# Wings_pwm.net
KiCad netlist of a schematic drawn in Altium Designer
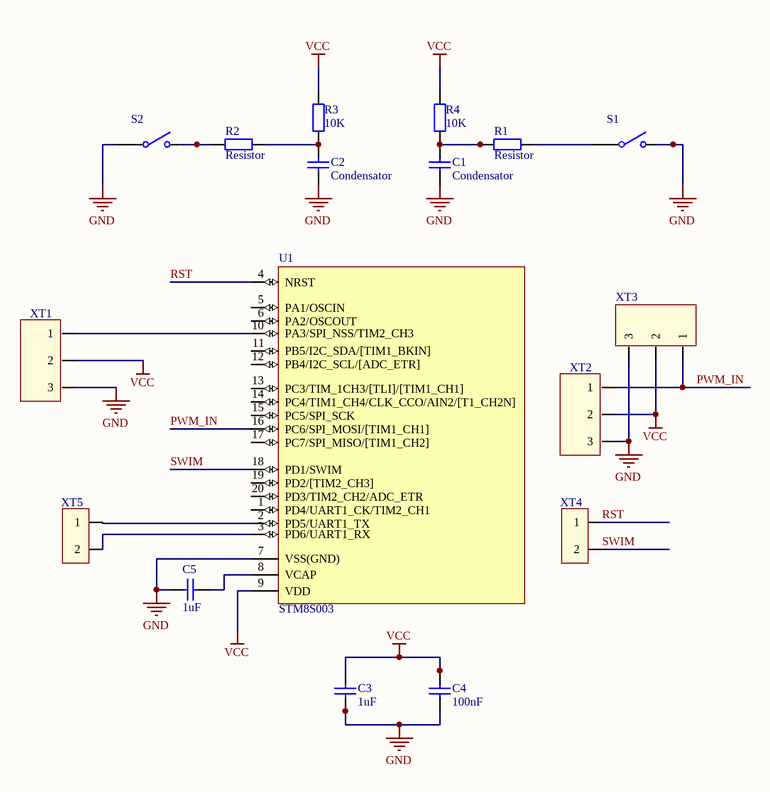
[diagram p0: Wings_pwm.SchDoc]

(export (version "E")
  (design (tool "Eeschema 10.0.6"))
  (components
    (comp (ref "C1")
      (value "Condensator")
      (footprint "A_H_pcb_lib:C0603")
      (libsource (lib "A_H_sch_lib") (part "Condensator"))
    )
    (comp (ref "C2")
      (value "Condensator")
      (footprint "A_H_pcb_lib:C0603")
      (libsource (lib "A_H_sch_lib") (part "Condensator"))
    )
    (comp (ref "C3")
      (value "1uF")
      (footprint "A_H_pcb_lib:C0603")
      (libsource (lib "A_H_sch_lib") (part "Condensator"))
    )
    (comp (ref "C4")
      (value "100nF")
      (footprint "A_H_pcb_lib:C0603")
      (libsource (lib "A_H_sch_lib") (part "Condensator"))
    )
    (comp (ref "C5")
      (value "1uF")
      (footprint "A_H_pcb_lib:C0603")
      (libsource (lib "A_H_sch_lib") (part "Condensator"))
    )
    (comp (ref "R1")
      (value "Resistor")
      (footprint "A_H_pcb_lib:R0603")
      (libsource (lib "A_H_sch_lib") (part "Resistor"))
    )
    (comp (ref "R2")
      (value "Resistor")
      (footprint "A_H_pcb_lib:R0603")
      (libsource (lib "A_H_sch_lib") (part "Resistor"))
    )
    (comp (ref "R3") (value "10K") (footprint "A_H_pcb_lib:R0603") (libsource (lib "") (part "Resistor_1")))
    (comp (ref "R4") (value "10K") (footprint "A_H_pcb_lib:R0603") (libsource (lib "") (part "Resistor_1")))
    (comp (ref "S1")
      (value "*")
      (footprint "A_H_pcb_lib:Tact_switch_smd")
      (libsource (lib "A_H_sch_lib") (part "Tact_switch"))
    )
    (comp (ref "S2")
      (value "*")
      (footprint "A_H_pcb_lib:Tact_switch_smd")
      (libsource (lib "A_H_sch_lib") (part "Tact_switch"))
    )
    (comp (ref "U1")
      (value "STM8S003")
      (footprint "A_H_pcb_lib:STM8S003_TSOP20")
      (libsource (lib "A_H_sch_lib") (part "STM8S003"))
    )
    (comp (ref "XT1")
      (value "*")
      (footprint "A_H_pcb_lib:flat_3pad")
      (libsource (lib "") (part "Pins 3x2.54_1"))
    )
    (comp (ref "XT2")
      (value "*")
      (footprint "A_H_pcb_lib:flat_3pad")
      (libsource (lib "") (part "Pins 3x2.54_1"))
    )
    (comp (ref "XT3")
      (value "*")
      (footprint "A_H_pcb_lib:flat_3pad")
      (libsource (lib "A_H_sch_lib") (part "Pins 3x2.54"))
    )
    (comp (ref "XT4")
      (value "*")
      (footprint "A_H_pcb_lib:Pins 2x2.54")
      (libsource (lib "A_H_sch_lib") (part "Pins 2x2.54"))
    )
    (comp (ref "XT5")
      (value "*")
      (footprint "A_H_pcb_lib:Pins 2x2.54")
      (libsource (lib "A_H_sch_lib") (part "Pins 2x2.54"))
    )
  )
  (nets
    (net (code "1") (name "/PWM_IN") (class "Default")
      (node (ref "U1") (pin "16") (pinfunction "PC6/SPI_MOSI/[TIM1_CH1]_16") (pintype "bidirectional"))
      (node (ref "XT2") (pin "1") (pinfunction "1_1") (pintype "passive"))
      (node (ref "XT3") (pin "1") (pinfunction "1_1") (pintype "passive"))
    )
    (net (code "2") (name "/RST") (class "Default")
      (node (ref "U1") (pin "4") (pinfunction "NRST_4") (pintype "bidirectional"))
      (node (ref "XT4") (pin "1") (pinfunction "1_1") (pintype "passive"))
    )
    (net (code "3") (name "/SWIM") (class "Default")
      (node (ref "U1") (pin "18") (pinfunction "PD1/SWIM_18") (pintype "bidirectional"))
      (node (ref "XT4") (pin "2") (pinfunction "2_2") (pintype "passive"))
    )
    (net (code "4") (name "GND") (class "Default")
      (node (ref "C1") (pin "1") (pinfunction "1_1") (pintype "passive"))
      (node (ref "C2") (pin "1") (pinfunction "1_1") (pintype "passive"))
      (node (ref "C3") (pin "2") (pinfunction "2_2") (pintype "passive"))
      (node (ref "C4") (pin "2") (pinfunction "2_2") (pintype "passive"))
      (node (ref "C5") (pin "2") (pinfunction "2_2") (pintype "passive"))
      (node (ref "S1") (pin "2") (pinfunction "NO_2") (pintype "passive"))
      (node (ref "S2") (pin "1") (pinfunction "COMMON_1") (pintype "passive"))
      (node (ref "U1") (pin "7") (pinfunction "VSS(GND)_7") (pintype "power_in"))
      (node (ref "XT1") (pin "3") (pinfunction "3_3") (pintype "passive"))
      (node (ref "XT2") (pin "3") (pinfunction "3_3") (pintype "passive"))
      (node (ref "XT3") (pin "3") (pinfunction "3_3") (pintype "passive"))
    )
    (net (code "5") (name "Net-(C1-Pad2)") (class "Default")
      (node (ref "C1") (pin "2") (pinfunction "2_2") (pintype "passive"))
      (node (ref "R1") (pin "1") (pinfunction "1_1") (pintype "passive"))
      (node (ref "R4") (pin "2") (pinfunction "2_2") (pintype "passive"))
    )
    (net (code "6") (name "Net-(C2-Pad2)") (class "Default")
      (node (ref "C2") (pin "2") (pinfunction "2_2") (pintype "passive"))
      (node (ref "R2") (pin "2") (pinfunction "2_2") (pintype "passive"))
      (node (ref "R3") (pin "2") (pinfunction "2_2") (pintype "passive"))
    )
    (net (code "7") (name "Net-(S1-COMMON)") (class "Default")
      (node (ref "R1") (pin "2") (pinfunction "2_2") (pintype "passive"))
      (node (ref "S1") (pin "1") (pinfunction "COMMON_1") (pintype "passive"))
    )
    (net (code "8") (name "Net-(S2-NO)") (class "Default")
      (node (ref "R2") (pin "1") (pinfunction "1_1") (pintype "passive"))
      (node (ref "S2") (pin "2") (pinfunction "NO_2") (pintype "passive"))
    )
    (net (code "9") (name "Net-(U1-PA3{slash}SPI_NSS{slash}TIM2_CH3)") (class "Default")
      (node (ref "U1") (pin "10") (pinfunction "PA3/SPI_NSS/TIM2_CH3_10") (pintype "bidirectional"))
      (node (ref "XT1") (pin "1") (pinfunction "1_1") (pintype "passive"))
    )
    (net (code "10") (name "Net-(U1-PD5{slash}UART1_TX)") (class "Default")
      (node (ref "U1") (pin "2") (pinfunction "PD5/UART1_TX_2") (pintype "bidirectional"))
      (node (ref "XT5") (pin "1") (pinfunction "1_1") (pintype "passive"))
    )
    (net (code "11") (name "Net-(U1-PD6{slash}UART1_RX)") (class "Default")
      (node (ref "U1") (pin "3") (pinfunction "PD6/UART1_RX_3") (pintype "bidirectional"))
      (node (ref "XT5") (pin "2") (pinfunction "2_2") (pintype "passive"))
    )
    (net (code "12") (name "Net-(U1-VCAP)") (class "Default")
      (node (ref "C5") (pin "1") (pinfunction "1_1") (pintype "passive"))
      (node (ref "U1") (pin "8") (pinfunction "VCAP_8") (pintype "power_in"))
    )
    (net (code "13") (name "VCC") (class "Default")
      (node (ref "C3") (pin "1") (pinfunction "1_1") (pintype "passive"))
      (node (ref "C4") (pin "1") (pinfunction "1_1") (pintype "passive"))
      (node (ref "R3") (pin "1") (pinfunction "1_1") (pintype "passive"))
      (node (ref "R4") (pin "1") (pinfunction "1_1") (pintype "passive"))
      (node (ref "U1") (pin "9") (pinfunction "VDD_9") (pintype "power_in"))
      (node (ref "XT1") (pin "2") (pinfunction "2_2") (pintype "passive"))
      (node (ref "XT2") (pin "2") (pinfunction "2_2") (pintype "passive"))
      (node (ref "XT3") (pin "2") (pinfunction "2_2") (pintype "passive"))
    )
    (net (code "14") (name "unconnected-(U1-PA1{slash}OSCIN-Pad5)") (class "Default")
      (node (ref "U1") (pin "5") (pinfunction "PA1/OSCIN_5") (pintype "bidirectional"))
    )
    (net (code "15") (name "unconnected-(U1-PA2{slash}OSCOUT-Pad6)") (class "Default")
      (node (ref "U1") (pin "6") (pinfunction "PA2/OSCOUT_6") (pintype "bidirectional"))
    )
    (net (code "16") (name "unconnected-(U1-PB4{slash}I2C_SCL{slash}[ADC_ETR]-Pad12)") (class "Default")
      (node (ref "U1") (pin "12") (pinfunction "PB4/I2C_SCL/[ADC_ETR]_12") (pintype "bidirectional"))
    )
    (net (code "17") (name "unconnected-(U1-PB5{slash}I2C_SDA{slash}[TIM1_BKIN]-Pad11)") (class "Default")
      (node (ref "U1") (pin "11") (pinfunction "PB5/I2C_SDA/[TIM1_BKIN]_11") (pintype "bidirectional"))
    )
    (net (code "18") (name "unconnected-(U1-PC3{slash}TIM_1CH3{slash}[TLI]{slash}[TIM1_CH1]-Pad13)") (class "Default")
      (node (ref "U1") (pin "13") (pinfunction "PC3/TIM_1CH3/[TLI]/[TIM1_CH1]_13") (pintype "bidirectional"))
    )
    (net (code "19") (name "unconnected-(U1-PC4{slash}TIM1_CH4{slash}CLK_CCO{slash}AIN2{slash}[T1_CH2N]-Pad14)") (class "Default")
      (node (ref "U1") (pin "14") (pinfunction "PC4/TIM1_CH4/CLK_CCO/AIN2/[T1_CH2N]_14") (pintype "bidirectional"))
    )
    (net (code "20") (name "unconnected-(U1-PC5{slash}SPI_SCK-Pad15)") (class "Default")
      (node (ref "U1") (pin "15") (pinfunction "PC5/SPI_SCK_15") (pintype "bidirectional"))
    )
    (net (code "21") (name "unconnected-(U1-PC7{slash}SPI_MISO{slash}[TIM1_CH2]-Pad17)") (class "Default")
      (node (ref "U1") (pin "17") (pinfunction "PC7/SPI_MISO/[TIM1_CH2]_17") (pintype "bidirectional"))
    )
    (net (code "22") (name "unconnected-(U1-PD2{slash}[TIM2_CH3]-Pad19)") (class "Default")
      (node (ref "U1") (pin "19") (pinfunction "PD2/[TIM2_CH3]_19") (pintype "bidirectional"))
    )
    (net (code "23") (name "unconnected-(U1-PD3{slash}TIM2_CH2{slash}ADC_ETR-Pad20)") (class "Default")
      (node (ref "U1") (pin "20") (pinfunction "PD3/TIM2_CH2/ADC_ETR_20") (pintype "bidirectional"))
    )
    (net (code "24") (name "unconnected-(U1-PD4{slash}UART1_CK{slash}TIM2_CH1-Pad1)") (class "Default")
      (node (ref "U1") (pin "1") (pinfunction "PD4/UART1_CK/TIM2_CH1_1") (pintype "bidirectional"))
    )
  )
)
